# VehicleDriverSchematics2.net
KiCad netlist of a schematic drawn in EAGLE
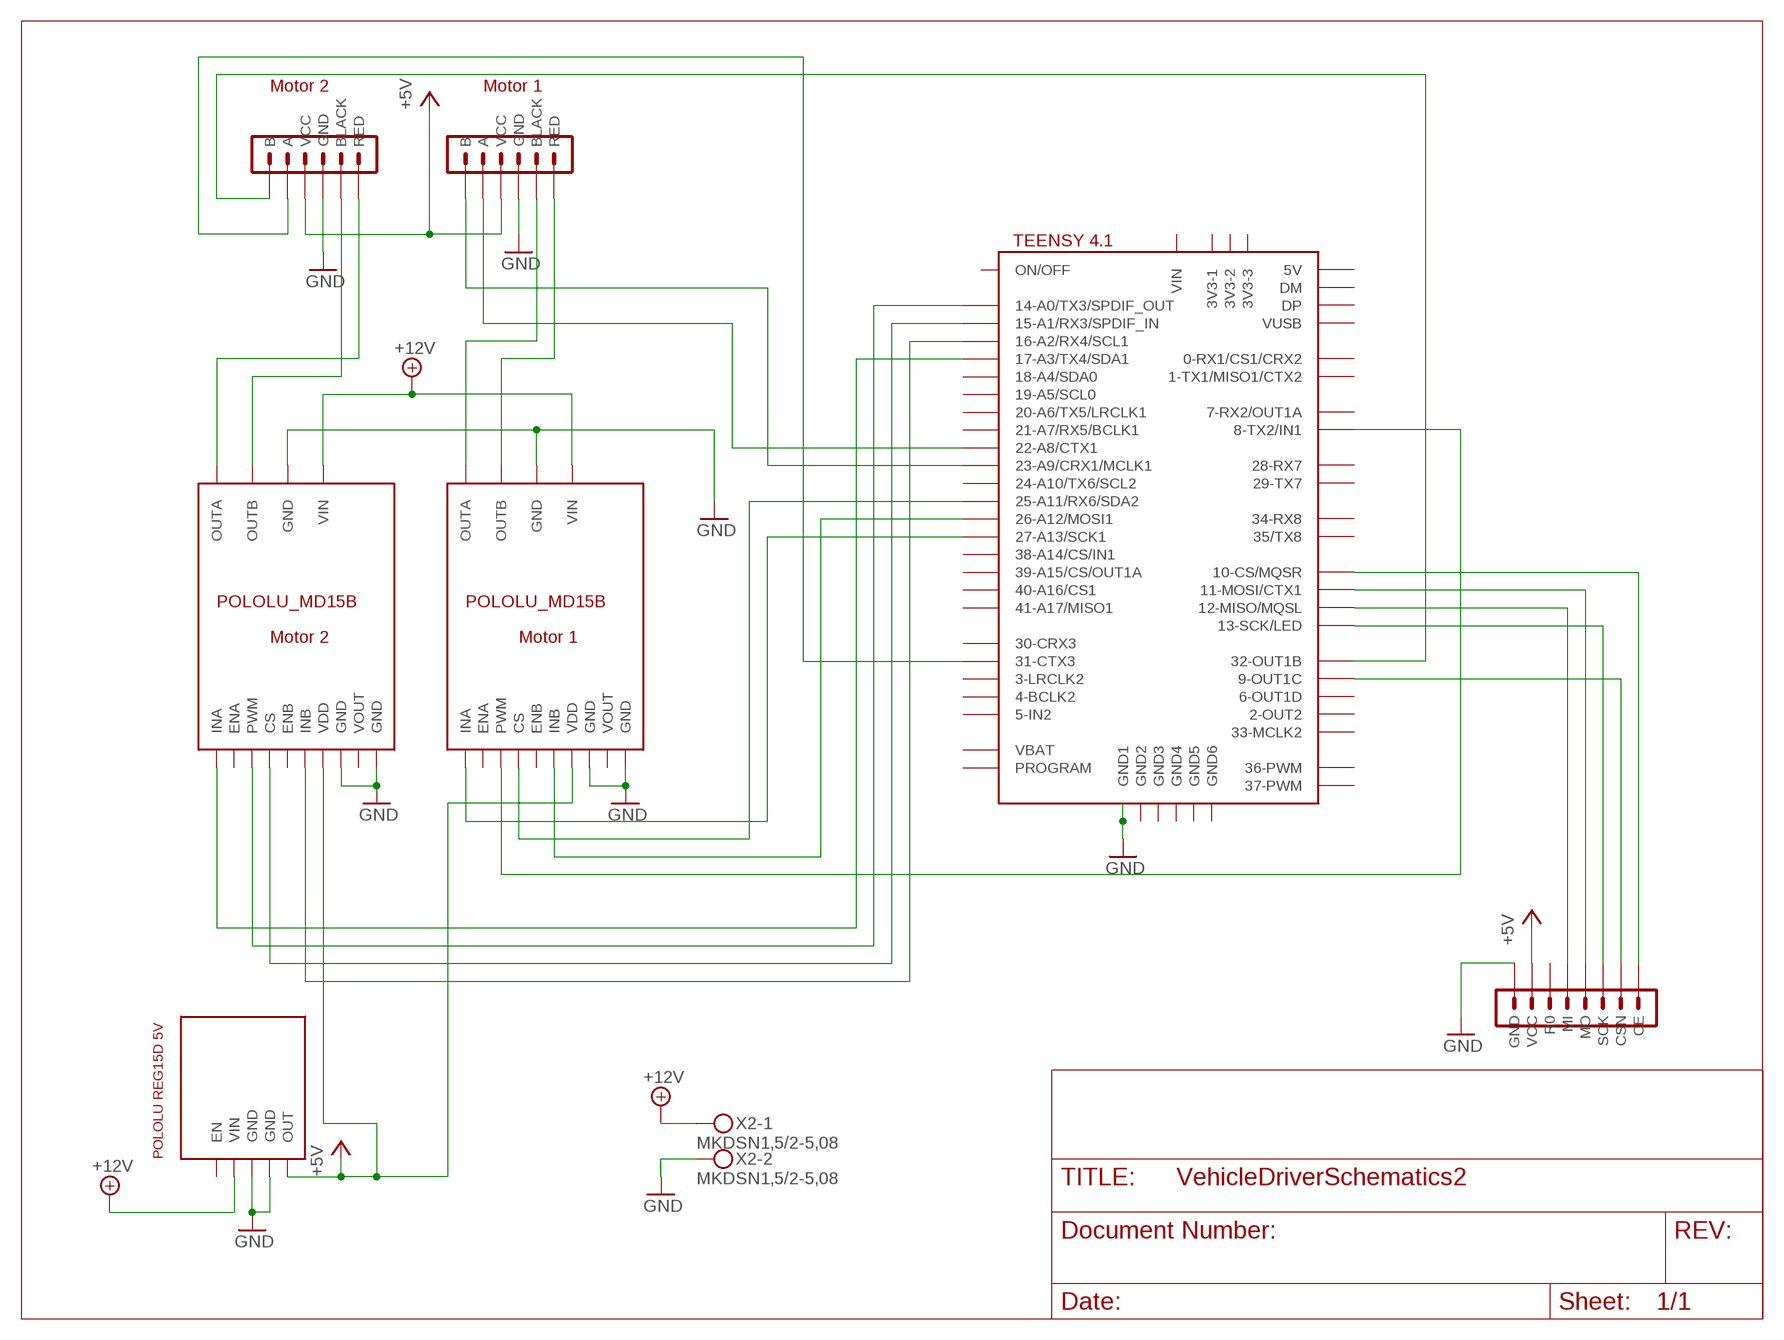
[diagram p0: schematic, sheet 1]

(export (version "E")
  (design (tool "Eeschema 10.0.6"))
  (components
    (comp (ref "U$2")
      (value "POLOLU_MD15B")
      (footprint "eagle-import:POLOLU_MD15B")
      (libsource (lib "eagle-import") (part "POLOLU_MD15B"))
    )
    (comp (ref "U$3")
      (value "POLOLU_MD15B")
      (footprint "eagle-import:POLOLU_MD15B")
      (libsource (lib "eagle-import") (part "POLOLU_MD15B"))
    )
    (comp (ref "U$4")
      (value "TEENSY41-E")
      (footprint "eagle-import:TENNSY41-E")
      (libsource (lib "eagle-import") (part "TEENSY41-E"))
    )
    (comp (ref "U$5")
      (value "MA06-1")
      (footprint "eagle-import:MA06-1")
      (libsource (lib "eagle-import") (part "MA06-1"))
    )
    (comp (ref "U$6")
      (value "MA06-1")
      (footprint "eagle-import:MA06-1")
      (libsource (lib "eagle-import") (part "MA06-1"))
    )
    (comp (ref "U$7")
      (value "MA08-1-RF24")
      (footprint "eagle-import:MA08-1-RF24")
      (libsource (lib "eagle-import") (part "MA08-1-RF24"))
    )
    (comp (ref "U$8")
      (value "POLOLU_REG15D")
      (footprint "eagle-import:POLOLU_REG15D")
      (libsource (lib "eagle-import") (part "POLOLU_REG15D"))
    )
    (comp (ref "X2")
      (value "MKDSN1,5/2-5,08")
      (footprint "eagle-import:MKDSN1,5_2-5,08")
      (libsource (lib "eagle-import") (part "MKDSN1,5/2-5,08"))
    )
  )
  (nets
    (net (code "1") (name "+5V") (class "Default")
      (node (ref "U$2") (pin "VDD") (pinfunction "VDD_VDD") (pintype "input"))
      (node (ref "U$3") (pin "VDD") (pinfunction "VDD_VDD") (pintype "input"))
      (node (ref "U$5") (pin "VCC") (pinfunction "VCC_VCC") (pintype "bidirectional"))
      (node (ref "U$6") (pin "VCC") (pinfunction "VCC_VCC") (pintype "bidirectional"))
      (node (ref "U$7") (pin "VCC") (pinfunction "VCC_VCC") (pintype "power_in"))
      (node (ref "U$8") (pin "OUT") (pinfunction "OUT_OUT") (pintype "output"))
    )
    (net (code "2") (name "+12V") (class "Default")
      (node (ref "U$2") (pin "VIN") (pinfunction "VIN_VIN") (pintype "input"))
      (node (ref "U$3") (pin "VIN") (pinfunction "VIN_VIN") (pintype "input"))
      (node (ref "U$8") (pin "VIN") (pinfunction "VIN_VIN") (pintype "power_in"))
      (node (ref "X2") (pin "1") (pinfunction "KL_1") (pintype "passive"))
    )
    (net (code "3") (name "GND") (class "Default")
      (node (ref "U$2") (pin "GND") (pinfunction "GND_GND") (pintype "bidirectional"))
      (node (ref "U$2") (pin "GND@1") (pinfunction "GND_GND@1") (pintype "bidirectional"))
      (node (ref "U$2") (pin "GND@2") (pinfunction "GND_GND@2") (pintype "bidirectional"))
      (node (ref "U$3") (pin "GND") (pinfunction "GND_GND") (pintype "bidirectional"))
      (node (ref "U$3") (pin "GND@1") (pinfunction "GND_GND@1") (pintype "bidirectional"))
      (node (ref "U$3") (pin "GND@2") (pinfunction "GND_GND@2") (pintype "bidirectional"))
      (node (ref "U$4") (pin "GND1") (pinfunction "GND1_GND1") (pintype "bidirectional"))
      (node (ref "U$5") (pin "GND") (pinfunction "GND_GND") (pintype "bidirectional"))
      (node (ref "U$6") (pin "GND") (pinfunction "GND_GND") (pintype "bidirectional"))
      (node (ref "U$7") (pin "GND") (pinfunction "GND_GND") (pintype "power_in"))
      (node (ref "U$8") (pin "GND") (pinfunction "GND_GND") (pintype "power_in"))
      (node (ref "U$8") (pin "GND@1") (pinfunction "GND_GND@1") (pintype "power_in"))
      (node (ref "X2") (pin "2") (pinfunction "KL_2") (pintype "passive"))
    )
    (net (code "4") (name "Net-(U$2-PadCS)") (class "Default")
      (node (ref "U$2") (pin "CS") (pinfunction "CS_CS") (pintype "input"))
      (node (ref "U$4") (pin "15-A1/RX3/SPDIF_IN") (pinfunction "15-A1/RX3/SPDIF_IN_15-A1/RX3/SPDIF_IN") (pintype "bidirectional"))
    )
    (net (code "5") (name "Net-(U$2-PadINA)") (class "Default")
      (node (ref "U$2") (pin "INA") (pinfunction "INA_INA") (pintype "input"))
      (node (ref "U$4") (pin "17-A3/TX4/SDA1") (pinfunction "17-A3/TX4/SDA1_17-A3/TX4/SDA1") (pintype "bidirectional"))
    )
    (net (code "6") (name "Net-(U$2-PadINB)") (class "Default")
      (node (ref "U$2") (pin "INB") (pinfunction "INB_INB") (pintype "input"))
      (node (ref "U$4") (pin "16-A2/RX4/SCL1") (pinfunction "16-A2/RX4/SCL1_16-A2/RX4/SCL1") (pintype "bidirectional"))
    )
    (net (code "7") (name "Net-(U$2-PadOUTA)") (class "Default")
      (node (ref "U$2") (pin "OUTA") (pinfunction "OUTA_OUTA") (pintype "output"))
      (node (ref "U$5") (pin "RED") (pinfunction "RED_RED") (pintype "input"))
    )
    (net (code "8") (name "Net-(U$2-PadOUTB)") (class "Default")
      (node (ref "U$2") (pin "OUTB") (pinfunction "OUTB_OUTB") (pintype "output"))
      (node (ref "U$5") (pin "BLACK") (pinfunction "BLACK_BLACK") (pintype "input"))
    )
    (net (code "9") (name "Net-(U$2-PadPWM)") (class "Default")
      (node (ref "U$2") (pin "PWM") (pinfunction "PWM_PWM") (pintype "bidirectional"))
      (node (ref "U$4") (pin "14-A0/TX3/SPDIF_OUT") (pinfunction "14-A0/TX3/SPDIF_OUT_14-A0/TX3/SPDIF_OUT") (pintype "bidirectional"))
    )
    (net (code "10") (name "Net-(U$3-PadCS)") (class "Default")
      (node (ref "U$3") (pin "CS") (pinfunction "CS_CS") (pintype "input"))
      (node (ref "U$4") (pin "25-A11/RX6/SDA2") (pinfunction "25-A11/RX6/SDA2_25-A11/RX6/SDA2") (pintype "bidirectional"))
    )
    (net (code "11") (name "Net-(U$3-PadINA)") (class "Default")
      (node (ref "U$3") (pin "INA") (pinfunction "INA_INA") (pintype "input"))
      (node (ref "U$4") (pin "27-A13/SCK1") (pinfunction "27-A13/SCK1_27-A13/SCK1") (pintype "bidirectional"))
    )
    (net (code "12") (name "Net-(U$3-PadINB)") (class "Default")
      (node (ref "U$3") (pin "INB") (pinfunction "INB_INB") (pintype "input"))
      (node (ref "U$4") (pin "26-A12/MOSI1") (pinfunction "26-A12/MOSI1_26-A12/MOSI1") (pintype "bidirectional"))
    )
    (net (code "13") (name "Net-(U$3-PadOUTA)") (class "Default")
      (node (ref "U$3") (pin "OUTA") (pinfunction "OUTA_OUTA") (pintype "output"))
      (node (ref "U$6") (pin "BLACK") (pinfunction "BLACK_BLACK") (pintype "input"))
    )
    (net (code "14") (name "Net-(U$3-PadOUTB)") (class "Default")
      (node (ref "U$3") (pin "OUTB") (pinfunction "OUTB_OUTB") (pintype "output"))
      (node (ref "U$6") (pin "RED") (pinfunction "RED_RED") (pintype "input"))
    )
    (net (code "15") (name "Net-(U$3-PadPWM)") (class "Default")
      (node (ref "U$3") (pin "PWM") (pinfunction "PWM_PWM") (pintype "bidirectional"))
      (node (ref "U$4") (pin "8-TX2/IN1") (pinfunction "8-TX2/IN1_8-TX2/IN1") (pintype "bidirectional"))
    )
    (net (code "16") (name "Net-(U$4-10-CS{slash}MQSR)") (class "Default")
      (node (ref "U$4") (pin "10-CS\\MQSR") (pinfunction "10-CS/MQSR_10-CS\\MQSR") (pintype "bidirectional"))
      (node (ref "U$7") (pin "CE") (pinfunction "CE_CE") (pintype "passive"))
    )
    (net (code "17") (name "Net-(U$4-Pad9-OUT1C)") (class "Default")
      (node (ref "U$4") (pin "9-OUT1C") (pinfunction "9-OUT1C_9-OUT1C") (pintype "bidirectional"))
      (node (ref "U$7") (pin "CSN") (pinfunction "CSN_CSN") (pintype "passive"))
    )
    (net (code "18") (name "Net-(U$4-Pad11-MOSI{slash}CTX1)") (class "Default")
      (node (ref "U$4") (pin "11-MOSI/CTX1") (pinfunction "11-MOSI/CTX1_11-MOSI/CTX1") (pintype "bidirectional"))
      (node (ref "U$7") (pin "MO") (pinfunction "MO_MO") (pintype "passive"))
    )
    (net (code "19") (name "Net-(U$4-Pad12-MISO{slash}MQSL)") (class "Default")
      (node (ref "U$4") (pin "12-MISO/MQSL") (pinfunction "12-MISO/MQSL_12-MISO/MQSL") (pintype "bidirectional"))
      (node (ref "U$7") (pin "MI") (pinfunction "MI_MI") (pintype "passive"))
    )
    (net (code "20") (name "Net-(U$4-Pad13-SCK{slash}LED)") (class "Default")
      (node (ref "U$4") (pin "13-SCK/LED") (pinfunction "13-SCK/LED_13-SCK/LED") (pintype "bidirectional"))
      (node (ref "U$7") (pin "SCK") (pinfunction "SCK_SCK") (pintype "passive"))
    )
    (net (code "21") (name "Net-(U$4-Pad22-A8{slash}CTX1)") (class "Default")
      (node (ref "U$4") (pin "22-A8/CTX1") (pinfunction "22-A8/CTX1_22-A8/CTX1") (pintype "bidirectional"))
      (node (ref "U$6") (pin "A") (pinfunction "A_A") (pintype "output"))
    )
    (net (code "22") (name "Net-(U$4-Pad23-A9{slash}CRX1{slash}MCLK1)") (class "Default")
      (node (ref "U$4") (pin "23-A9/CRX1/MCLK1") (pinfunction "23-A9/CRX1/MCLK1_23-A9/CRX1/MCLK1") (pintype "bidirectional"))
      (node (ref "U$6") (pin "B") (pinfunction "B_B") (pintype "output"))
    )
    (net (code "23") (name "Net-(U$4-Pad31-CTX3)") (class "Default")
      (node (ref "U$4") (pin "31-CTX3") (pinfunction "31-CTX3_31-CTX3") (pintype "bidirectional"))
      (node (ref "U$5") (pin "A") (pinfunction "A_A") (pintype "output"))
    )
    (net (code "24") (name "Net-(U$4-Pad32-OUT1B)") (class "Default")
      (node (ref "U$4") (pin "32-OUT1B") (pinfunction "32-OUT1B_32-OUT1B") (pintype "bidirectional"))
      (node (ref "U$5") (pin "B") (pinfunction "B_B") (pintype "output"))
    )
    (net (code "25") (name "unconnected-(U$2-PadENA)") (class "Default")
      (node (ref "U$2") (pin "ENA") (pinfunction "ENA_ENA") (pintype "input"))
    )
    (net (code "26") (name "unconnected-(U$2-PadENB)") (class "Default")
      (node (ref "U$2") (pin "ENB") (pinfunction "ENB_ENB") (pintype "input"))
    )
    (net (code "27") (name "unconnected-(U$2-PadVOUT)") (class "Default")
      (node (ref "U$2") (pin "VOUT") (pinfunction "VOUT_VOUT") (pintype "bidirectional"))
    )
    (net (code "28") (name "unconnected-(U$3-PadENA)") (class "Default")
      (node (ref "U$3") (pin "ENA") (pinfunction "ENA_ENA") (pintype "input"))
    )
    (net (code "29") (name "unconnected-(U$3-PadENB)") (class "Default")
      (node (ref "U$3") (pin "ENB") (pinfunction "ENB_ENB") (pintype "input"))
    )
    (net (code "30") (name "unconnected-(U$3-PadVOUT)") (class "Default")
      (node (ref "U$3") (pin "VOUT") (pinfunction "VOUT_VOUT") (pintype "bidirectional"))
    )
    (net (code "31") (name "unconnected-(U$4-5V-Pad+5V)") (class "Default")
      (node (ref "U$4") (pin "+5V") (pinfunction "5V_+5V") (pintype "bidirectional"))
    )
    (net (code "32") (name "unconnected-(U$4-35{slash}TX8-Pad35-TX8)") (class "Default")
      (node (ref "U$4") (pin "35-TX8") (pinfunction "35/TX8_35-TX8") (pintype "bidirectional"))
    )
    (net (code "33") (name "unconnected-(U$4-Pad0-RX1{slash}CS1{slash}CRX2)") (class "Default")
      (node (ref "U$4") (pin "0-RX1/CS1/CRX2") (pinfunction "0-RX1/CS1/CRX2_0-RX1/CS1/CRX2") (pintype "bidirectional"))
    )
    (net (code "34") (name "unconnected-(U$4-Pad1-TX1{slash}MISO1{slash}CTX2)") (class "Default")
      (node (ref "U$4") (pin "1-TX1/MISO1/CTX2") (pinfunction "1-TX1/MISO1/CTX2_1-TX1/MISO1/CTX2") (pintype "bidirectional"))
    )
    (net (code "35") (name "unconnected-(U$4-Pad2-OUT2)") (class "Default")
      (node (ref "U$4") (pin "2-OUT2") (pinfunction "2-OUT2_2-OUT2") (pintype "bidirectional"))
    )
    (net (code "36") (name "unconnected-(U$4-Pad3-LRCLK2)") (class "Default")
      (node (ref "U$4") (pin "3-LRCLK2") (pinfunction "3-LRCLK2_3-LRCLK2") (pintype "bidirectional"))
    )
    (net (code "37") (name "unconnected-(U$4-Pad3V3-1)") (class "Default")
      (node (ref "U$4") (pin "3V3-1") (pinfunction "3V3-1_3V3-1") (pintype "bidirectional"))
    )
    (net (code "38") (name "unconnected-(U$4-Pad3V3-2)") (class "Default")
      (node (ref "U$4") (pin "3V3-2") (pinfunction "3V3-2_3V3-2") (pintype "bidirectional"))
    )
    (net (code "39") (name "unconnected-(U$4-Pad3V3-3)") (class "Default")
      (node (ref "U$4") (pin "3V3-3") (pinfunction "3V3-3_3V3-3") (pintype "bidirectional"))
    )
    (net (code "40") (name "unconnected-(U$4-Pad4-BCLK2)") (class "Default")
      (node (ref "U$4") (pin "4-BCLK2") (pinfunction "4-BCLK2_4-BCLK2") (pintype "bidirectional"))
    )
    (net (code "41") (name "unconnected-(U$4-Pad5-IN2)") (class "Default")
      (node (ref "U$4") (pin "5-IN2") (pinfunction "5-IN2_5-IN2") (pintype "bidirectional"))
    )
    (net (code "42") (name "unconnected-(U$4-Pad6-OUT1D)") (class "Default")
      (node (ref "U$4") (pin "6-OUT1D") (pinfunction "6-OUT1D_6-OUT1D") (pintype "bidirectional"))
    )
    (net (code "43") (name "unconnected-(U$4-Pad7-RX2{slash}OUT1A)") (class "Default")
      (node (ref "U$4") (pin "7-RX2/OUT1A") (pinfunction "7-RX2/OUT1A_7-RX2/OUT1A") (pintype "bidirectional"))
    )
    (net (code "44") (name "unconnected-(U$4-Pad18-A4{slash}SDA0)") (class "Default")
      (node (ref "U$4") (pin "18-A4/SDA0") (pinfunction "18-A4/SDA0_18-A4/SDA0") (pintype "bidirectional"))
    )
    (net (code "45") (name "unconnected-(U$4-Pad19-A5{slash}SCL0)") (class "Default")
      (node (ref "U$4") (pin "19-A5/SCL0") (pinfunction "19-A5/SCL0_19-A5/SCL0") (pintype "bidirectional"))
    )
    (net (code "46") (name "unconnected-(U$4-Pad20-A6{slash}TX5{slash}LRCLK1)") (class "Default")
      (node (ref "U$4") (pin "20-A6/TX5/LRCLK1") (pinfunction "20-A6/TX5/LRCLK1_20-A6/TX5/LRCLK1") (pintype "bidirectional"))
    )
    (net (code "47") (name "unconnected-(U$4-Pad21-A7{slash}RX5{slash}BCLK1)") (class "Default")
      (node (ref "U$4") (pin "21-A7/RX5/BCLK1") (pinfunction "21-A7/RX5/BCLK1_21-A7/RX5/BCLK1") (pintype "bidirectional"))
    )
    (net (code "48") (name "unconnected-(U$4-Pad24-A10{slash}TX6{slash}SCL2)") (class "Default")
      (node (ref "U$4") (pin "24-A10/TX6/SCL2") (pinfunction "24-A10/TX6/SCL2_24-A10/TX6/SCL2") (pintype "bidirectional"))
    )
    (net (code "49") (name "unconnected-(U$4-Pad28-RX7)") (class "Default")
      (node (ref "U$4") (pin "28-RX7") (pinfunction "28-RX7_28-RX7") (pintype "bidirectional"))
    )
    (net (code "50") (name "unconnected-(U$4-Pad29-TX7)") (class "Default")
      (node (ref "U$4") (pin "29-TX7") (pinfunction "29-TX7_29-TX7") (pintype "bidirectional"))
    )
    (net (code "51") (name "unconnected-(U$4-Pad30-CRX3)") (class "Default")
      (node (ref "U$4") (pin "30-CRX3") (pinfunction "30-CRX3_30-CRX3") (pintype "bidirectional"))
    )
    (net (code "52") (name "unconnected-(U$4-Pad33-MCLK2)") (class "Default")
      (node (ref "U$4") (pin "33-MCLK2") (pinfunction "33-MCLK2_33-MCLK2") (pintype "bidirectional"))
    )
    (net (code "53") (name "unconnected-(U$4-Pad34-RX8)") (class "Default")
      (node (ref "U$4") (pin "34-RX8") (pinfunction "34-RX8_34-RX8") (pintype "bidirectional"))
    )
    (net (code "54") (name "unconnected-(U$4-Pad36-PWM)") (class "Default")
      (node (ref "U$4") (pin "36-PWM") (pinfunction "36-PWM_36-PWM") (pintype "bidirectional"))
    )
    (net (code "55") (name "unconnected-(U$4-Pad37-PWM)") (class "Default")
      (node (ref "U$4") (pin "37-PWM") (pinfunction "37-PWM_37-PWM") (pintype "bidirectional"))
    )
    (net (code "56") (name "unconnected-(U$4-Pad38-A14{slash}CS{slash}IN1)") (class "Default")
      (node (ref "U$4") (pin "38-A14/CS/IN1") (pinfunction "38-A14/CS/IN1_38-A14/CS/IN1") (pintype "bidirectional"))
    )
    (net (code "57") (name "unconnected-(U$4-Pad39-A15{slash}CS{slash}OUT1A)") (class "Default")
      (node (ref "U$4") (pin "39-A15/CS/OUT1A") (pinfunction "39-A15/CS/OUT1A_39-A15/CS/OUT1A") (pintype "bidirectional"))
    )
    (net (code "58") (name "unconnected-(U$4-Pad40-A16{slash}CS1)") (class "Default")
      (node (ref "U$4") (pin "40-A16/CS1") (pinfunction "40-A16/CS1_40-A16/CS1") (pintype "bidirectional"))
    )
    (net (code "59") (name "unconnected-(U$4-Pad41-A17{slash}MISO1)") (class "Default")
      (node (ref "U$4") (pin "41-A17/MISO1") (pinfunction "41-A17/MISO1_41-A17/MISO1") (pintype "bidirectional"))
    )
    (net (code "60") (name "unconnected-(U$4-PadDM)") (class "Default")
      (node (ref "U$4") (pin "DM") (pinfunction "DM_DM") (pintype "bidirectional"))
    )
    (net (code "61") (name "unconnected-(U$4-PadDP)") (class "Default")
      (node (ref "U$4") (pin "DP") (pinfunction "DP_DP") (pintype "bidirectional"))
    )
    (net (code "62") (name "unconnected-(U$4-PadGND2)") (class "Default")
      (node (ref "U$4") (pin "GND2") (pinfunction "GND2_GND2") (pintype "bidirectional"))
    )
    (net (code "63") (name "unconnected-(U$4-PadGND3)") (class "Default")
      (node (ref "U$4") (pin "GND3") (pinfunction "GND3_GND3") (pintype "bidirectional"))
    )
    (net (code "64") (name "unconnected-(U$4-PadGND4)") (class "Default")
      (node (ref "U$4") (pin "GND4") (pinfunction "GND4_GND4") (pintype "bidirectional"))
    )
    (net (code "65") (name "unconnected-(U$4-PadGND5)") (class "Default")
      (node (ref "U$4") (pin "GND5") (pinfunction "GND5_GND5") (pintype "bidirectional"))
    )
    (net (code "66") (name "unconnected-(U$4-PadGND6)") (class "Default")
      (node (ref "U$4") (pin "GND6") (pinfunction "GND6_GND6") (pintype "bidirectional"))
    )
    (net (code "67") (name "unconnected-(U$4-PadON{slash}OFF)") (class "Default")
      (node (ref "U$4") (pin "ON/OFF") (pinfunction "ON/OFF_ON/OFF") (pintype "bidirectional"))
    )
    (net (code "68") (name "unconnected-(U$4-PadPROGRAM)") (class "Default")
      (node (ref "U$4") (pin "PROGRAM") (pinfunction "PROGRAM_PROGRAM") (pintype "bidirectional"))
    )
    (net (code "69") (name "unconnected-(U$4-PadVBAT)") (class "Default")
      (node (ref "U$4") (pin "VBAT") (pinfunction "VBAT_VBAT") (pintype "bidirectional"))
    )
    (net (code "70") (name "unconnected-(U$4-PadVIN)") (class "Default")
      (node (ref "U$4") (pin "VIN") (pinfunction "VIN_VIN") (pintype "bidirectional"))
    )
    (net (code "71") (name "unconnected-(U$4-PadVUSB)") (class "Default")
      (node (ref "U$4") (pin "VUSB") (pinfunction "VUSB_VUSB") (pintype "bidirectional"))
    )
    (net (code "72") (name "unconnected-(U$7-PadR0)") (class "Default")
      (node (ref "U$7") (pin "R0") (pinfunction "R0_R0") (pintype "passive"))
    )
    (net (code "73") (name "unconnected-(U$8-PadEN)") (class "Default")
      (node (ref "U$8") (pin "EN") (pinfunction "EN_EN") (pintype "input"))
    )
  )
)
